# PCB-DISPARRAY4b.net
KiCad netlist of a schematic drawn in EAGLE
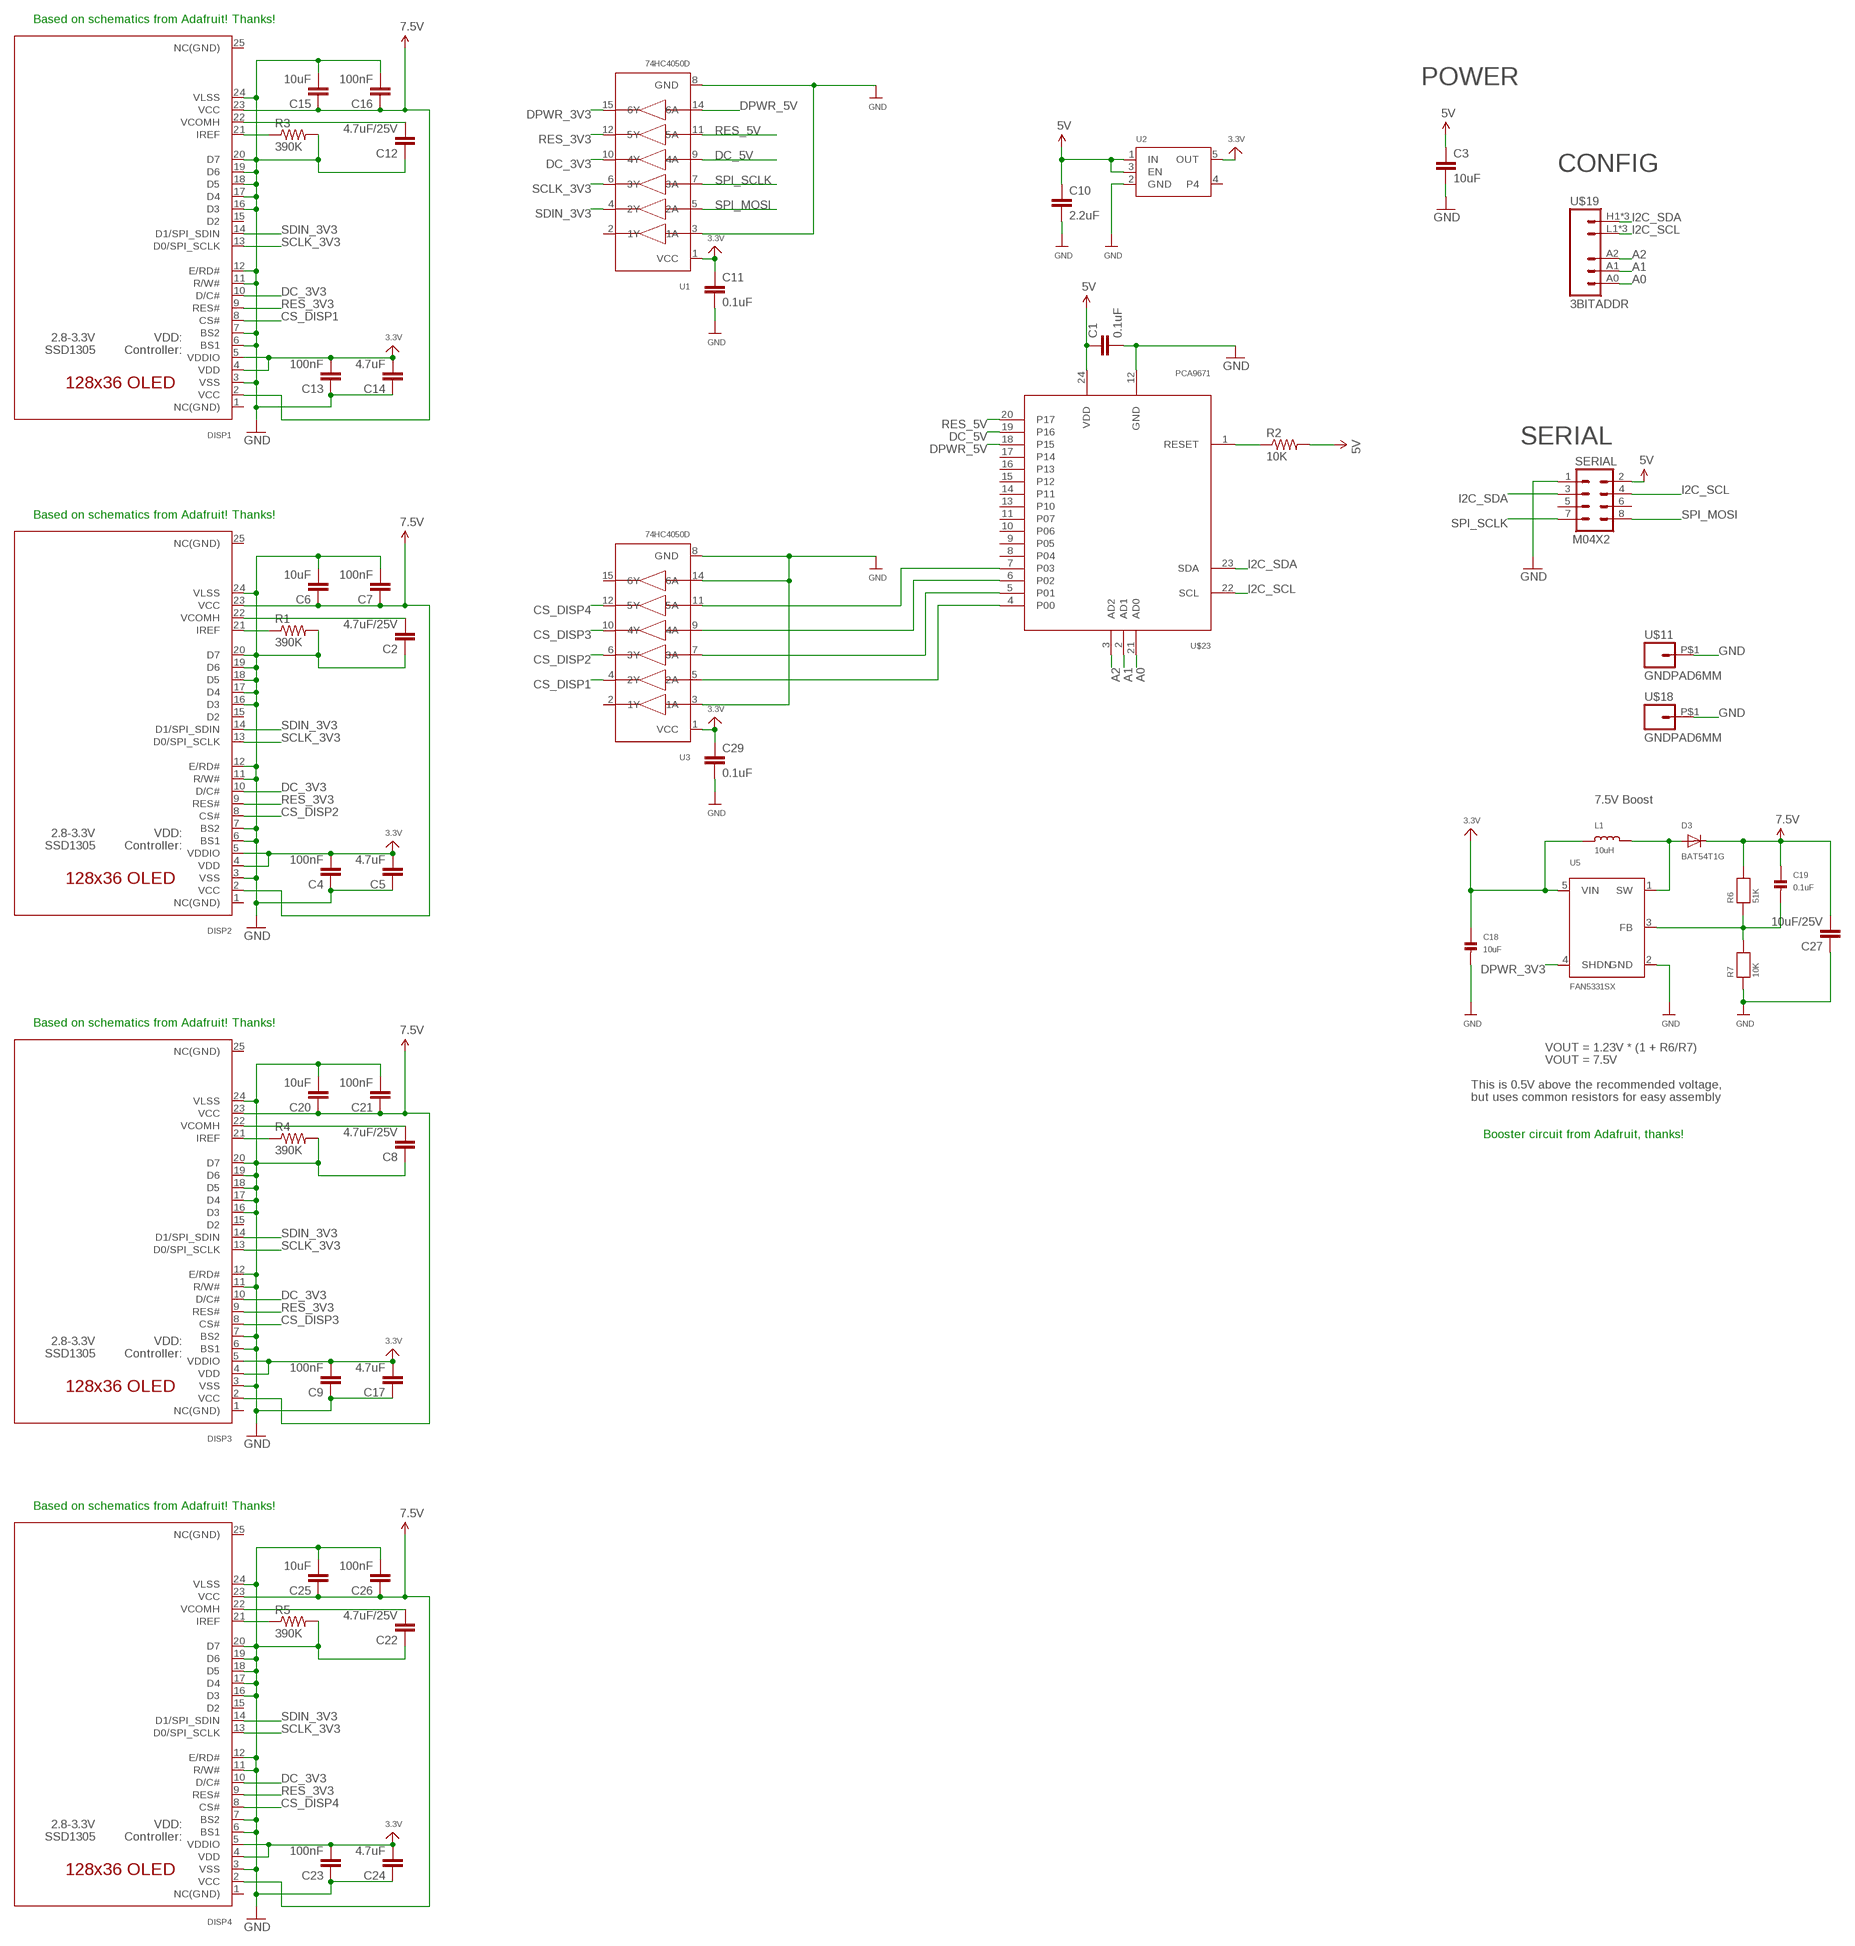
[diagram p0: schematic, sheet 1]

(export (version "E")
  (design (tool "Eeschema 10.0.6"))
  (components
    (comp (ref "C1")
      (value "0.1uF")
      (footprint "eagle-import:0603-CAP")
      (libsource (lib "eagle-import") (part "CAP0603-CAP"))
    )
    (comp (ref "C2")
      (value "4.7uF/25V")
      (footprint "eagle-import:0805")
      (libsource (lib "eagle-import") (part "CAP0805"))
    )
    (comp (ref "C3")
      (value "10uF")
      (footprint "eagle-import:0805")
      (libsource (lib "eagle-import") (part "CAP0805"))
    )
    (comp (ref "C4")
      (value "100nF")
      (footprint "eagle-import:0603-CAP")
      (libsource (lib "eagle-import") (part "CAP0603-CAP"))
    )
    (comp (ref "C5")
      (value "4.7uF")
      (footprint "eagle-import:0603-CAP")
      (libsource (lib "eagle-import") (part "CAP0603-CAP"))
    )
    (comp (ref "C6")
      (value "10uF")
      (footprint "eagle-import:0805")
      (libsource (lib "eagle-import") (part "CAP0805"))
    )
    (comp (ref "C7")
      (value "100nF")
      (footprint "eagle-import:0603-CAP")
      (libsource (lib "eagle-import") (part "CAP0603-CAP"))
    )
    (comp (ref "C8")
      (value "4.7uF/25V")
      (footprint "eagle-import:0805")
      (libsource (lib "eagle-import") (part "CAP0805"))
    )
    (comp (ref "C9")
      (value "100nF")
      (footprint "eagle-import:0603-CAP")
      (libsource (lib "eagle-import") (part "CAP0603-CAP"))
    )
    (comp (ref "C10")
      (value "2.2uF")
      (footprint "eagle-import:0603-CAP")
      (libsource (lib "eagle-import") (part "CAP0603-CAP"))
    )
    (comp (ref "C11")
      (value "0.1uF")
      (footprint "eagle-import:0603-CAP")
      (libsource (lib "eagle-import") (part "CAP0603-CAP"))
    )
    (comp (ref "C12")
      (value "4.7uF/25V")
      (footprint "eagle-import:0805")
      (libsource (lib "eagle-import") (part "CAP0805"))
    )
    (comp (ref "C13")
      (value "100nF")
      (footprint "eagle-import:0603-CAP")
      (libsource (lib "eagle-import") (part "CAP0603-CAP"))
    )
    (comp (ref "C14")
      (value "4.7uF")
      (footprint "eagle-import:0603-CAP")
      (libsource (lib "eagle-import") (part "CAP0603-CAP"))
    )
    (comp (ref "C15")
      (value "10uF")
      (footprint "eagle-import:0805")
      (libsource (lib "eagle-import") (part "CAP0805"))
    )
    (comp (ref "C16")
      (value "100nF")
      (footprint "eagle-import:0603-CAP")
      (libsource (lib "eagle-import") (part "CAP0603-CAP"))
    )
    (comp (ref "C17")
      (value "4.7uF")
      (footprint "eagle-import:0603-CAP")
      (libsource (lib "eagle-import") (part "CAP0603-CAP"))
    )
    (comp (ref "C18")
      (value "10uF")
      (footprint "eagle-import:0805")
      (libsource (lib "eagle-import") (part "CAP_CERAMIC0805"))
    )
    (comp (ref "C19")
      (value "0.1uF")
      (footprint "eagle-import:0603")
      (libsource (lib "eagle-import") (part "CAP_CERAMIC0603"))
    )
    (comp (ref "C20")
      (value "10uF")
      (footprint "eagle-import:0805")
      (libsource (lib "eagle-import") (part "CAP0805"))
    )
    (comp (ref "C21")
      (value "100nF")
      (footprint "eagle-import:0603-CAP")
      (libsource (lib "eagle-import") (part "CAP0603-CAP"))
    )
    (comp (ref "C22")
      (value "4.7uF/25V")
      (footprint "eagle-import:0805")
      (libsource (lib "eagle-import") (part "CAP0805"))
    )
    (comp (ref "C23")
      (value "100nF")
      (footprint "eagle-import:0603-CAP")
      (libsource (lib "eagle-import") (part "CAP0603-CAP"))
    )
    (comp (ref "C24")
      (value "4.7uF")
      (footprint "eagle-import:0603-CAP")
      (libsource (lib "eagle-import") (part "CAP0603-CAP"))
    )
    (comp (ref "C25")
      (value "10uF")
      (footprint "eagle-import:0805")
      (libsource (lib "eagle-import") (part "CAP0805"))
    )
    (comp (ref "C26")
      (value "100nF")
      (footprint "eagle-import:0603-CAP")
      (libsource (lib "eagle-import") (part "CAP0603-CAP"))
    )
    (comp (ref "C27")
      (value "10uF/25V")
      (footprint "eagle-import:0805")
      (libsource (lib "eagle-import") (part "CAP0805"))
    )
    (comp (ref "C29")
      (value "0.1uF")
      (footprint "eagle-import:0603-CAP")
      (libsource (lib "eagle-import") (part "CAP0603-CAP"))
    )
    (comp (ref "D3")
      (value "BAT54T1G")
      (footprint "eagle-import:SOD-123")
      (libsource (lib "eagle-import") (part "DIODESOD-123"))
    )
    (comp (ref "DISP1")
      (value "ER-OLED011-1TOP")
      (footprint "eagle-import:ER-OLED011-1")
      (libsource (lib "eagle-import") (part "ER-OLED011-1TOP"))
    )
    (comp (ref "DISP2")
      (value "ER-OLED011-1TOP")
      (footprint "eagle-import:ER-OLED011-1")
      (libsource (lib "eagle-import") (part "ER-OLED011-1TOP"))
    )
    (comp (ref "DISP3")
      (value "ER-OLED011-1TOP")
      (footprint "eagle-import:ER-OLED011-1")
      (libsource (lib "eagle-import") (part "ER-OLED011-1TOP"))
    )
    (comp (ref "DISP4")
      (value "ER-OLED011-1TOP")
      (footprint "eagle-import:ER-OLED011-1")
      (libsource (lib "eagle-import") (part "ER-OLED011-1TOP"))
    )
    (comp (ref "L1")
      (value "10uH")
      (footprint "eagle-import:INDUCTOR_1007")
      (libsource (lib "eagle-import") (part "INDUCTOR"))
    )
    (comp (ref "R1")
      (value "390K")
      (footprint "eagle-import:0603-RES")
      (libsource (lib "eagle-import") (part "RESISTOR0603-RES"))
    )
    (comp (ref "R2")
      (value "10K")
      (footprint "eagle-import:0603-RES")
      (libsource (lib "eagle-import") (part "RESISTOR0603-RES"))
    )
    (comp (ref "R3")
      (value "390K")
      (footprint "eagle-import:0603-RES")
      (libsource (lib "eagle-import") (part "RESISTOR0603-RES"))
    )
    (comp (ref "R4")
      (value "390K")
      (footprint "eagle-import:0603-RES")
      (libsource (lib "eagle-import") (part "RESISTOR0603-RES"))
    )
    (comp (ref "R5")
      (value "390K")
      (footprint "eagle-import:0603-RES")
      (libsource (lib "eagle-import") (part "RESISTOR0603-RES"))
    )
    (comp (ref "R6")
      (value "51K")
      (footprint "eagle-import:0603")
      (libsource (lib "eagle-import") (part "RESISTOR0603"))
    )
    (comp (ref "R7")
      (value "10K")
      (footprint "eagle-import:0603")
      (libsource (lib "eagle-import") (part "RESISTOR0603"))
    )
    (comp (ref "SERIAL")
      (value "M04X2")
      (footprint "eagle-import:2X4")
      (libsource (lib "eagle-import") (part "M04X2"))
    )
    (comp (ref "U$11")
      (value "GNDPAD6MM")
      (footprint "eagle-import:3.2MMPAD6MM")
      (libsource (lib "eagle-import") (part "GNDPAD6MM"))
    )
    (comp (ref "U$18")
      (value "GNDPAD6MM")
      (footprint "eagle-import:3.2MMPAD6MM")
      (libsource (lib "eagle-import") (part "GNDPAD6MM"))
    )
    (comp (ref "U$19")
      (value "3BITADDR")
      (footprint "eagle-import:3BITADDR")
      (libsource (lib "eagle-import") (part "3BITADDR"))
    )
    (comp (ref "U$23")
      (value "PCA9671")
      (footprint "eagle-import:TSSOP24")
      (libsource (lib "eagle-import") (part "PCA9671"))
    )
    (comp (ref "U1")
      (value "74HC4050D")
      (footprint "eagle-import:TSSOP16")
      (libsource (lib "eagle-import") (part "74HC4050DTSSOP16"))
    )
    (comp (ref "U2")
      (value "VREG_SOT23-5")
      (footprint "eagle-import:SOT23-5")
      (libsource (lib "eagle-import") (part "VREG_SOT23-5"))
    )
    (comp (ref "U3")
      (value "74HC4050D")
      (footprint "eagle-import:TSSOP16")
      (libsource (lib "eagle-import") (part "74HC4050DTSSOP16"))
    )
    (comp (ref "U5")
      (value "FAN5331SX")
      (footprint "eagle-import:SOT23-5")
      (libsource (lib "eagle-import") (part "FAN5331"))
    )
  )
  (nets
    (net (code "1") (name "3.3V") (class "Default")
      (node (ref "C11") (pin "1") (pinfunction "1_1") (pintype "passive"))
      (node (ref "C13") (pin "2") (pinfunction "2_2") (pintype "passive"))
      (node (ref "C14") (pin "2") (pinfunction "2_2") (pintype "passive"))
      (node (ref "C17") (pin "2") (pinfunction "2_2") (pintype "passive"))
      (node (ref "C18") (pin "1") (pinfunction "P$1_1") (pintype "passive"))
      (node (ref "C23") (pin "2") (pinfunction "2_2") (pintype "passive"))
      (node (ref "C24") (pin "2") (pinfunction "2_2") (pintype "passive"))
      (node (ref "C29") (pin "1") (pinfunction "1_1") (pintype "passive"))
      (node (ref "C4") (pin "2") (pinfunction "2_2") (pintype "passive"))
      (node (ref "C5") (pin "2") (pinfunction "2_2") (pintype "passive"))
      (node (ref "C9") (pin "2") (pinfunction "2_2") (pintype "passive"))
      (node (ref "DISP1") (pin "4") (pinfunction "VDD_4") (pintype "power_in"))
      (node (ref "DISP1") (pin "5") (pinfunction "VDDIO_5") (pintype "power_in"))
      (node (ref "DISP2") (pin "4") (pinfunction "VDD_4") (pintype "power_in"))
      (node (ref "DISP2") (pin "5") (pinfunction "VDDIO_5") (pintype "power_in"))
      (node (ref "DISP3") (pin "4") (pinfunction "VDD_4") (pintype "power_in"))
      (node (ref "DISP3") (pin "5") (pinfunction "VDDIO_5") (pintype "power_in"))
      (node (ref "DISP4") (pin "4") (pinfunction "VDD_4") (pintype "power_in"))
      (node (ref "DISP4") (pin "5") (pinfunction "VDDIO_5") (pintype "power_in"))
      (node (ref "L1") (pin "P$1") (pinfunction "1_P$1") (pintype "passive"))
      (node (ref "U1") (pin "1") (pinfunction "VCC_1") (pintype "bidirectional"))
      (node (ref "U2") (pin "5") (pinfunction "OUT_5") (pintype "bidirectional"))
      (node (ref "U3") (pin "1") (pinfunction "VCC_1") (pintype "bidirectional"))
      (node (ref "U5") (pin "5") (pinfunction "VIN_5") (pintype "bidirectional"))
    )
    (net (code "2") (name "5V") (class "Default")
      (node (ref "C1") (pin "1") (pinfunction "1_1") (pintype "passive"))
      (node (ref "C10") (pin "1") (pinfunction "1_1") (pintype "passive"))
      (node (ref "C3") (pin "1") (pinfunction "1_1") (pintype "passive"))
      (node (ref "R2") (pin "2") (pinfunction "2_2") (pintype "passive"))
      (node (ref "SERIAL") (pin "2") (pinfunction "2_2") (pintype "passive"))
      (node (ref "U$23") (pin "24") (pinfunction "VDD_24") (pintype "power_in"))
      (node (ref "U2") (pin "1") (pinfunction "IN_1") (pintype "bidirectional"))
      (node (ref "U2") (pin "3") (pinfunction "EN_3") (pintype "bidirectional"))
    )
    (net (code "3") (name "7.5V") (class "Default")
      (node (ref "C15") (pin "1") (pinfunction "1_1") (pintype "passive"))
      (node (ref "C16") (pin "1") (pinfunction "1_1") (pintype "passive"))
      (node (ref "C19") (pin "1") (pinfunction "P$1_1") (pintype "passive"))
      (node (ref "C20") (pin "1") (pinfunction "1_1") (pintype "passive"))
      (node (ref "C21") (pin "1") (pinfunction "1_1") (pintype "passive"))
      (node (ref "C25") (pin "1") (pinfunction "1_1") (pintype "passive"))
      (node (ref "C26") (pin "1") (pinfunction "1_1") (pintype "passive"))
      (node (ref "C27") (pin "2") (pinfunction "2_2") (pintype "passive"))
      (node (ref "C6") (pin "1") (pinfunction "1_1") (pintype "passive"))
      (node (ref "C7") (pin "1") (pinfunction "1_1") (pintype "passive"))
      (node (ref "D3") (pin "C") (pinfunction "C_C") (pintype "passive"))
      (node (ref "DISP1") (pin "2") (pinfunction "VCC_2") (pintype "power_in"))
      (node (ref "DISP1") (pin "23") (pinfunction "VCC_23") (pintype "power_in"))
      (node (ref "DISP2") (pin "2") (pinfunction "VCC_2") (pintype "power_in"))
      (node (ref "DISP2") (pin "23") (pinfunction "VCC_23") (pintype "power_in"))
      (node (ref "DISP3") (pin "2") (pinfunction "VCC_2") (pintype "power_in"))
      (node (ref "DISP3") (pin "23") (pinfunction "VCC_23") (pintype "power_in"))
      (node (ref "DISP4") (pin "2") (pinfunction "VCC_2") (pintype "power_in"))
      (node (ref "DISP4") (pin "23") (pinfunction "VCC_23") (pintype "power_in"))
      (node (ref "R6") (pin "2") (pinfunction "2_2") (pintype "passive"))
    )
    (net (code "4") (name "A0") (class "Default")
      (node (ref "U$19") (pin "A0") (pinfunction "A0_A0") (pintype "passive"))
      (node (ref "U$23") (pin "21") (pinfunction "AD0_21") (pintype "input"))
    )
    (net (code "5") (name "A1") (class "Default")
      (node (ref "U$19") (pin "A1") (pinfunction "A1_A1") (pintype "passive"))
      (node (ref "U$23") (pin "2") (pinfunction "AD1_2") (pintype "input"))
    )
    (net (code "6") (name "A2") (class "Default")
      (node (ref "U$19") (pin "A2") (pinfunction "A2_A2") (pintype "passive"))
      (node (ref "U$23") (pin "3") (pinfunction "AD2_3") (pintype "input"))
    )
    (net (code "7") (name "CS_DISP1") (class "Default")
      (node (ref "DISP1") (pin "8") (pinfunction "CS#_8") (pintype "input"))
      (node (ref "U3") (pin "4") (pinfunction "2Y_4") (pintype "bidirectional"))
    )
    (net (code "8") (name "CS_DISP2") (class "Default")
      (node (ref "DISP2") (pin "8") (pinfunction "CS#_8") (pintype "input"))
      (node (ref "U3") (pin "6") (pinfunction "3Y_6") (pintype "bidirectional"))
    )
    (net (code "9") (name "CS_DISP3") (class "Default")
      (node (ref "DISP3") (pin "8") (pinfunction "CS#_8") (pintype "input"))
      (node (ref "U3") (pin "10") (pinfunction "4Y_10") (pintype "bidirectional"))
    )
    (net (code "10") (name "CS_DISP4") (class "Default")
      (node (ref "DISP4") (pin "8") (pinfunction "CS#_8") (pintype "input"))
      (node (ref "U3") (pin "12") (pinfunction "5Y_12") (pintype "bidirectional"))
    )
    (net (code "11") (name "DC_3V3") (class "Default")
      (node (ref "DISP1") (pin "10") (pinfunction "D/C#_10") (pintype "input"))
      (node (ref "DISP2") (pin "10") (pinfunction "D/C#_10") (pintype "input"))
      (node (ref "DISP3") (pin "10") (pinfunction "D/C#_10") (pintype "input"))
      (node (ref "DISP4") (pin "10") (pinfunction "D/C#_10") (pintype "input"))
      (node (ref "U1") (pin "10") (pinfunction "4Y_10") (pintype "bidirectional"))
    )
    (net (code "12") (name "DC_5V") (class "Default")
      (node (ref "U$23") (pin "19") (pinfunction "P16_19") (pintype "output"))
      (node (ref "U1") (pin "9") (pinfunction "4A_9") (pintype "bidirectional"))
    )
    (net (code "13") (name "DPWR_3V3") (class "Default")
      (node (ref "U1") (pin "15") (pinfunction "6Y_15") (pintype "bidirectional"))
      (node (ref "U5") (pin "4") (pinfunction "SHDN_4") (pintype "bidirectional"))
    )
    (net (code "14") (name "DPWR_5V") (class "Default")
      (node (ref "U$23") (pin "18") (pinfunction "P15_18") (pintype "output"))
      (node (ref "U1") (pin "14") (pinfunction "6A_14") (pintype "bidirectional"))
    )
    (net (code "15") (name "GND") (class "Default")
      (node (ref "C1") (pin "2") (pinfunction "2_2") (pintype "passive"))
      (node (ref "C10") (pin "2") (pinfunction "2_2") (pintype "passive"))
      (node (ref "C11") (pin "2") (pinfunction "2_2") (pintype "passive"))
      (node (ref "C12") (pin "1") (pinfunction "1_1") (pintype "passive"))
      (node (ref "C13") (pin "1") (pinfunction "1_1") (pintype "passive"))
      (node (ref "C14") (pin "1") (pinfunction "1_1") (pintype "passive"))
      (node (ref "C15") (pin "2") (pinfunction "2_2") (pintype "passive"))
      (node (ref "C16") (pin "2") (pinfunction "2_2") (pintype "passive"))
      (node (ref "C17") (pin "1") (pinfunction "1_1") (pintype "passive"))
      (node (ref "C18") (pin "2") (pinfunction "P$2_2") (pintype "passive"))
      (node (ref "C2") (pin "1") (pinfunction "1_1") (pintype "passive"))
      (node (ref "C20") (pin "2") (pinfunction "2_2") (pintype "passive"))
      (node (ref "C21") (pin "2") (pinfunction "2_2") (pintype "passive"))
      (node (ref "C22") (pin "1") (pinfunction "1_1") (pintype "passive"))
      (node (ref "C23") (pin "1") (pinfunction "1_1") (pintype "passive"))
      (node (ref "C24") (pin "1") (pinfunction "1_1") (pintype "passive"))
      (node (ref "C25") (pin "2") (pinfunction "2_2") (pintype "passive"))
      (node (ref "C26") (pin "2") (pinfunction "2_2") (pintype "passive"))
      (node (ref "C27") (pin "1") (pinfunction "1_1") (pintype "passive"))
      (node (ref "C29") (pin "2") (pinfunction "2_2") (pintype "passive"))
      (node (ref "C3") (pin "2") (pinfunction "2_2") (pintype "passive"))
      (node (ref "C4") (pin "1") (pinfunction "1_1") (pintype "passive"))
      (node (ref "C5") (pin "1") (pinfunction "1_1") (pintype "passive"))
      (node (ref "C6") (pin "2") (pinfunction "2_2") (pintype "passive"))
      (node (ref "C7") (pin "2") (pinfunction "2_2") (pintype "passive"))
      (node (ref "C8") (pin "1") (pinfunction "1_1") (pintype "passive"))
      (node (ref "C9") (pin "1") (pinfunction "1_1") (pintype "passive"))
      (node (ref "DISP1") (pin "11") (pinfunction "R/W#_11") (pintype "input"))
      (node (ref "DISP1") (pin "12") (pinfunction "E/RD#_12") (pintype "input"))
      (node (ref "DISP1") (pin "16") (pinfunction "D3_16") (pintype "bidirectional"))
      (node (ref "DISP1") (pin "17") (pinfunction "D4_17") (pintype "bidirectional"))
      (node (ref "DISP1") (pin "18") (pinfunction "D5_18") (pintype "bidirectional"))
      (node (ref "DISP1") (pin "19") (pinfunction "D6_19") (pintype "bidirectional"))
      (node (ref "DISP1") (pin "20") (pinfunction "D7_20") (pintype "bidirectional"))
      (node (ref "DISP1") (pin "24") (pinfunction "VLSS_24") (pintype "power_in"))
      (node (ref "DISP1") (pin "3") (pinfunction "VSS_3") (pintype "power_in"))
      (node (ref "DISP1") (pin "6") (pinfunction "BS1_6") (pintype "input"))
      (node (ref "DISP1") (pin "7") (pinfunction "BS2_7") (pintype "input"))
      (node (ref "DISP2") (pin "11") (pinfunction "R/W#_11") (pintype "input"))
      (node (ref "DISP2") (pin "12") (pinfunction "E/RD#_12") (pintype "input"))
      (node (ref "DISP2") (pin "16") (pinfunction "D3_16") (pintype "bidirectional"))
      (node (ref "DISP2") (pin "17") (pinfunction "D4_17") (pintype "bidirectional"))
      (node (ref "DISP2") (pin "18") (pinfunction "D5_18") (pintype "bidirectional"))
      (node (ref "DISP2") (pin "19") (pinfunction "D6_19") (pintype "bidirectional"))
      (node (ref "DISP2") (pin "20") (pinfunction "D7_20") (pintype "bidirectional"))
      (node (ref "DISP2") (pin "24") (pinfunction "VLSS_24") (pintype "power_in"))
      (node (ref "DISP2") (pin "3") (pinfunction "VSS_3") (pintype "power_in"))
      (node (ref "DISP2") (pin "6") (pinfunction "BS1_6") (pintype "input"))
      (node (ref "DISP2") (pin "7") (pinfunction "BS2_7") (pintype "input"))
      (node (ref "DISP3") (pin "11") (pinfunction "R/W#_11") (pintype "input"))
      (node (ref "DISP3") (pin "12") (pinfunction "E/RD#_12") (pintype "input"))
      (node (ref "DISP3") (pin "16") (pinfunction "D3_16") (pintype "bidirectional"))
      (node (ref "DISP3") (pin "17") (pinfunction "D4_17") (pintype "bidirectional"))
      (node (ref "DISP3") (pin "18") (pinfunction "D5_18") (pintype "bidirectional"))
      (node (ref "DISP3") (pin "19") (pinfunction "D6_19") (pintype "bidirectional"))
      (node (ref "DISP3") (pin "20") (pinfunction "D7_20") (pintype "bidirectional"))
      (node (ref "DISP3") (pin "24") (pinfunction "VLSS_24") (pintype "power_in"))
      (node (ref "DISP3") (pin "3") (pinfunction "VSS_3") (pintype "power_in"))
      (node (ref "DISP3") (pin "6") (pinfunction "BS1_6") (pintype "input"))
      (node (ref "DISP3") (pin "7") (pinfunction "BS2_7") (pintype "input"))
      (node (ref "DISP4") (pin "11") (pinfunction "R/W#_11") (pintype "input"))
      (node (ref "DISP4") (pin "12") (pinfunction "E/RD#_12") (pintype "input"))
      (node (ref "DISP4") (pin "16") (pinfunction "D3_16") (pintype "bidirectional"))
      (node (ref "DISP4") (pin "17") (pinfunction "D4_17") (pintype "bidirectional"))
      (node (ref "DISP4") (pin "18") (pinfunction "D5_18") (pintype "bidirectional"))
      (node (ref "DISP4") (pin "19") (pinfunction "D6_19") (pintype "bidirectional"))
      (node (ref "DISP4") (pin "20") (pinfunction "D7_20") (pintype "bidirectional"))
      (node (ref "DISP4") (pin "24") (pinfunction "VLSS_24") (pintype "power_in"))
      (node (ref "DISP4") (pin "3") (pinfunction "VSS_3") (pintype "power_in"))
      (node (ref "DISP4") (pin "6") (pinfunction "BS1_6") (pintype "input"))
      (node (ref "DISP4") (pin "7") (pinfunction "BS2_7") (pintype "input"))
      (node (ref "R1") (pin "2") (pinfunction "2_2") (pintype "passive"))
      (node (ref "R3") (pin "2") (pinfunction "2_2") (pintype "passive"))
      (node (ref "R4") (pin "2") (pinfunction "2_2") (pintype "passive"))
      (node (ref "R5") (pin "2") (pinfunction "2_2") (pintype "passive"))
      (node (ref "R7") (pin "1") (pinfunction "1_1") (pintype "passive"))
      (node (ref "SERIAL") (pin "1") (pinfunction "1_1") (pintype "passive"))
      (node (ref "U$11") (pin "P$1") (pinfunction "1_P$1") (pintype "passive"))
      (node (ref "U$18") (pin "P$1") (pinfunction "1_P$1") (pintype "passive"))
      (node (ref "U$23") (pin "12") (pinfunction "GND_12") (pintype "power_in"))
      (node (ref "U1") (pin "3") (pinfunction "1A_3") (pintype "bidirectional"))
      (node (ref "U1") (pin "8") (pinfunction "GND_8") (pintype "bidirectional"))
      (node (ref "U2") (pin "2") (pinfunction "GND_2") (pintype "bidirectional"))
      (node (ref "U3") (pin "14") (pinfunction "6A_14") (pintype "bidirectional"))
      (node (ref "U3") (pin "3") (pinfunction "1A_3") (pintype "bidirectional"))
      (node (ref "U3") (pin "8") (pinfunction "GND_8") (pintype "bidirectional"))
      (node (ref "U5") (pin "2") (pinfunction "GND_2") (pintype "bidirectional"))
    )
    (net (code "16") (name "I2C_SCL") (class "Default")
      (node (ref "SERIAL") (pin "4") (pinfunction "4_4") (pintype "passive"))
      (node (ref "U$19") (pin "L1") (pinfunction "GND_L1") (pintype "passive"))
      (node (ref "U$19") (pin "L2") (pinfunction "GND_L2") (pintype "passive"))
      (node (ref "U$19") (pin "L3") (pinfunction "GND_L3") (pintype "passive"))
      (node (ref "U$23") (pin "22") (pinfunction "SCL_22") (pintype "input"))
    )
    (net (code "17") (name "I2C_SDA") (class "Default")
      (node (ref "SERIAL") (pin "3") (pinfunction "3_3") (pintype "passive"))
      (node (ref "U$19") (pin "H1") (pinfunction "VCC_H1") (pintype "passive"))
      (node (ref "U$19") (pin "H2") (pinfunction "VCC_H2") (pintype "passive"))
      (node (ref "U$19") (pin "H3") (pinfunction "VCC_H3") (pintype "passive"))
      (node (ref "U$23") (pin "23") (pinfunction "SDA_23") (pintype "input"))
    )
    (net (code "18") (name "Net-(C19-P$2)") (class "Default")
      (node (ref "C19") (pin "2") (pinfunction "P$2_2") (pintype "passive"))
      (node (ref "R6") (pin "1") (pinfunction "1_1") (pintype "passive"))
      (node (ref "R7") (pin "2") (pinfunction "2_2") (pintype "passive"))
      (node (ref "U5") (pin "3") (pinfunction "FB_3") (pintype "bidirectional"))
    )
    (net (code "19") (name "Net-(DISP1-IREF)") (class "Default")
      (node (ref "DISP1") (pin "21") (pinfunction "IREF_21") (pintype "input"))
      (node (ref "R3") (pin "1") (pinfunction "1_1") (pintype "passive"))
    )
    (net (code "20") (name "Net-(DISP1-VCOMH)") (class "Default")
      (node (ref "C12") (pin "2") (pinfunction "2_2") (pintype "passive"))
      (node (ref "DISP1") (pin "22") (pinfunction "VCOMH_22") (pintype "output"))
    )
    (net (code "21") (name "Net-(DISP2-IREF)") (class "Default")
      (node (ref "DISP2") (pin "21") (pinfunction "IREF_21") (pintype "input"))
      (node (ref "R1") (pin "1") (pinfunction "1_1") (pintype "passive"))
    )
    (net (code "22") (name "Net-(DISP2-VCOMH)") (class "Default")
      (node (ref "C2") (pin "2") (pinfunction "2_2") (pintype "passive"))
      (node (ref "DISP2") (pin "22") (pinfunction "VCOMH_22") (pintype "output"))
    )
    (net (code "23") (name "Net-(DISP3-IREF)") (class "Default")
      (node (ref "DISP3") (pin "21") (pinfunction "IREF_21") (pintype "input"))
      (node (ref "R4") (pin "1") (pinfunction "1_1") (pintype "passive"))
    )
    (net (code "24") (name "Net-(DISP3-VCOMH)") (class "Default")
      (node (ref "C8") (pin "2") (pinfunction "2_2") (pintype "passive"))
      (node (ref "DISP3") (pin "22") (pinfunction "VCOMH_22") (pintype "output"))
    )
    (net (code "25") (name "Net-(DISP4-IREF)") (class "Default")
      (node (ref "DISP4") (pin "21") (pinfunction "IREF_21") (pintype "input"))
      (node (ref "R5") (pin "1") (pinfunction "1_1") (pintype "passive"))
    )
    (net (code "26") (name "Net-(DISP4-VCOMH)") (class "Default")
      (node (ref "C22") (pin "2") (pinfunction "2_2") (pintype "passive"))
      (node (ref "DISP4") (pin "22") (pinfunction "VCOMH_22") (pintype "output"))
    )
    (net (code "27") (name "Net-(L1-2)") (class "Default")
      (node (ref "D3") (pin "A") (pinfunction "A_A") (pintype "passive"))
      (node (ref "L1") (pin "P$2") (pinfunction "2_P$2") (pintype "passive"))
      (node (ref "U5") (pin "1") (pinfunction "SW_1") (pintype "bidirectional"))
    )
    (net (code "28") (name "Net-(U$23-P00)") (class "Default")
      (node (ref "U$23") (pin "4") (pinfunction "P00_4") (pintype "output"))
      (node (ref "U3") (pin "5") (pinfunction "2A_5") (pintype "bidirectional"))
    )
    (net (code "29") (name "Net-(U$23-P01)") (class "Default")
      (node (ref "U$23") (pin "5") (pinfunction "P01_5") (pintype "output"))
      (node (ref "U3") (pin "7") (pinfunction "3A_7") (pintype "bidirectional"))
    )
    (net (code "30") (name "Net-(U$23-P02)") (class "Default")
      (node (ref "U$23") (pin "6") (pinfunction "P02_6") (pintype "output"))
      (node (ref "U3") (pin "9") (pinfunction "4A_9") (pintype "bidirectional"))
    )
    (net (code "31") (name "Net-(U$23-P03)") (class "Default")
      (node (ref "U$23") (pin "7") (pinfunction "P03_7") (pintype "output"))
      (node (ref "U3") (pin "11") (pinfunction "5A_11") (pintype "bidirectional"))
    )
    (net (code "32") (name "Net-(U$23-RESET)") (class "Default")
      (node (ref "R2") (pin "1") (pinfunction "1_1") (pintype "passive"))
      (node (ref "U$23") (pin "1") (pinfunction "RESET_1") (pintype "input"))
    )
    (net (code "33") (name "RES_3V3") (class "Default")
      (node (ref "DISP1") (pin "9") (pinfunction "RES#_9") (pintype "input"))
      (node (ref "DISP2") (pin "9") (pinfunction "RES#_9") (pintype "input"))
      (node (ref "DISP3") (pin "9") (pinfunction "RES#_9") (pintype "input"))
      (node (ref "DISP4") (pin "9") (pinfunction "RES#_9") (pintype "input"))
      (node (ref "U1") (pin "12") (pinfunction "5Y_12") (pintype "bidirectional"))
    )
    (net (code "34") (name "RES_5V") (class "Default")
      (node (ref "U$23") (pin "20") (pinfunction "P17_20") (pintype "output"))
      (node (ref "U1") (pin "11") (pinfunction "5A_11") (pintype "bidirectional"))
    )
    (net (code "35") (name "SCLK_3V3") (class "Default")
      (node (ref "DISP1") (pin "13") (pinfunction "D0/SPI_SCLK_13") (pintype "bidirectional"))
      (node (ref "DISP2") (pin "13") (pinfunction "D0/SPI_SCLK_13") (pintype "bidirectional"))
      (node (ref "DISP3") (pin "13") (pinfunction "D0/SPI_SCLK_13") (pintype "bidirectional"))
      (node (ref "DISP4") (pin "13") (pinfunction "D0/SPI_SCLK_13") (pintype "bidirectional"))
      (node (ref "U1") (pin "6") (pinfunction "3Y_6") (pintype "bidirectional"))
    )
    (net (code "36") (name "SDIN_3V3") (class "Default")
      (node (ref "DISP1") (pin "14") (pinfunction "D1/SPI_SDIN_14") (pintype "bidirectional"))
      (node (ref "DISP2") (pin "14") (pinfunction "D1/SPI_SDIN_14") (pintype "bidirectional"))
      (node (ref "DISP3") (pin "14") (pinfunction "D1/SPI_SDIN_14") (pintype "bidirectional"))
      (node (ref "DISP4") (pin "14") (pinfunction "D1/SPI_SDIN_14") (pintype "bidirectional"))
      (node (ref "U1") (pin "4") (pinfunction "2Y_4") (pintype "bidirectional"))
    )
    (net (code "37") (name "SPI_MOSI") (class "Default")
      (node (ref "SERIAL") (pin "8") (pinfunction "8_8") (pintype "passive"))
      (node (ref "U1") (pin "5") (pinfunction "2A_5") (pintype "bidirectional"))
    )
    (net (code "38") (name "SPI_SCLK") (class "Default")
      (node (ref "SERIAL") (pin "7") (pinfunction "7_7") (pintype "passive"))
      (node (ref "U1") (pin "7") (pinfunction "3A_7") (pintype "bidirectional"))
    )
    (net (code "39") (name "unconnected-(DISP1-D2-Pad15)") (class "Default")
      (node (ref "DISP1") (pin "15") (pinfunction "D2_15") (pintype "bidirectional"))
    )
    (net (code "40") (name "unconnected-(DISP1-NC(GND)-Pad1)") (class "Default")
      (node (ref "DISP1") (pin "1") (pinfunction "NC(GND)_1") (pintype "input"))
    )
    (net (code "41") (name "unconnected-(DISP1-NC(GND)-Pad25)") (class "Default")
      (node (ref "DISP1") (pin "25") (pinfunction "NC(GND)_25") (pintype "input"))
    )
    (net (code "42") (name "unconnected-(DISP2-D2-Pad15)") (class "Default")
      (node (ref "DISP2") (pin "15") (pinfunction "D2_15") (pintype "bidirectional"))
    )
    (net (code "43") (name "unconnected-(DISP2-NC(GND)-Pad1)") (class "Default")
      (node (ref "DISP2") (pin "1") (pinfunction "NC(GND)_1") (pintype "input"))
    )
    (net (code "44") (name "unconnected-(DISP2-NC(GND)-Pad25)") (class "Default")
      (node (ref "DISP2") (pin "25") (pinfunction "NC(GND)_25") (pintype "input"))
    )
    (net (code "45") (name "unconnected-(DISP3-D2-Pad15)") (class "Default")
      (node (ref "DISP3") (pin "15") (pinfunction "D2_15") (pintype "bidirectional"))
    )
    (net (code "46") (name "unconnected-(DISP3-NC(GND)-Pad1)") (class "Default")
      (node (ref "DISP3") (pin "1") (pinfunction "NC(GND)_1") (pintype "input"))
    )
    (net (code "47") (name "unconnected-(DISP3-NC(GND)-Pad25)") (class "Default")
      (node (ref "DISP3") (pin "25") (pinfunction "NC(GND)_25") (pintype "input"))
    )
    (net (code "48") (name "unconnected-(DISP4-D2-Pad15)") (class "Default")
      (node (ref "DISP4") (pin "15") (pinfunction "D2_15") (pintype "bidirectional"))
    )
    (net (code "49") (name "unconnected-(DISP4-NC(GND)-Pad1)") (class "Default")
      (node (ref "DISP4") (pin "1") (pinfunction "NC(GND)_1") (pintype "input"))
    )
    (net (code "50") (name "unconnected-(DISP4-NC(GND)-Pad25)") (class "Default")
      (node (ref "DISP4") (pin "25") (pinfunction "NC(GND)_25") (pintype "input"))
    )
    (net (code "51") (name "unconnected-(SERIAL-Pad5)") (class "Default")
      (node (ref "SERIAL") (pin "5") (pinfunction "5_5") (pintype "passive"))
    )
    (net (code "52") (name "unconnected-(SERIAL-Pad6)") (class "Default")
      (node (ref "SERIAL") (pin "6") (pinfunction "6_6") (pintype "passive"))
    )
    (net (code "53") (name "unconnected-(U$23-P04-Pad8)") (class "Default")
      (node (ref "U$23") (pin "8") (pinfunction "P04_8") (pintype "output"))
    )
    (net (code "54") (name "unconnected-(U$23-P05-Pad9)") (class "Default")
      (node (ref "U$23") (pin "9") (pinfunction "P05_9") (pintype "output"))
    )
    (net (code "55") (name "unconnected-(U$23-P06-Pad10)") (class "Default")
      (node (ref "U$23") (pin "10") (pinfunction "P06_10") (pintype "output"))
    )
    (net (code "56") (name "unconnected-(U$23-P07-Pad11)") (class "Default")
      (node (ref "U$23") (pin "11") (pinfunction "P07_11") (pintype "output"))
    )
    (net (code "57") (name "unconnected-(U$23-P10-Pad13)") (class "Default")
      (node (ref "U$23") (pin "13") (pinfunction "P10_13") (pintype "output"))
    )
    (net (code "58") (name "unconnected-(U$23-P11-Pad14)") (class "Default")
      (node (ref "U$23") (pin "14") (pinfunction "P11_14") (pintype "output"))
    )
    (net (code "59") (name "unconnected-(U$23-P12-Pad15)") (class "Default")
      (node (ref "U$23") (pin "15") (pinfunction "P12_15") (pintype "output"))
    )
    (net (code "60") (name "unconnected-(U$23-P13-Pad16)") (class "Default")
      (node (ref "U$23") (pin "16") (pinfunction "P13_16") (pintype "output"))
    )
    (net (code "61") (name "unconnected-(U$23-P14-Pad17)") (class "Default")
      (node (ref "U$23") (pin "17") (pinfunction "P14_17") (pintype "output"))
    )
    (net (code "62") (name "unconnected-(U1-1Y-Pad2)") (class "Default")
      (node (ref "U1") (pin "2") (pinfunction "1Y_2") (pintype "bidirectional"))
    )
    (net (code "63") (name "unconnected-(U2-P4-Pad4)") (class "Default")
      (node (ref "U2") (pin "4") (pinfunction "P4_4") (pintype "bidirectional"))
    )
    (net (code "64") (name "unconnected-(U3-1Y-Pad2)") (class "Default")
      (node (ref "U3") (pin "2") (pinfunction "1Y_2") (pintype "bidirectional"))
    )
    (net (code "65") (name "unconnected-(U3-6Y-Pad15)") (class "Default")
      (node (ref "U3") (pin "15") (pinfunction "6Y_15") (pintype "bidirectional"))
    )
  )
)
